# Subsheets_combined.net
KiCad netlist of a schematic drawn in Altium Designer
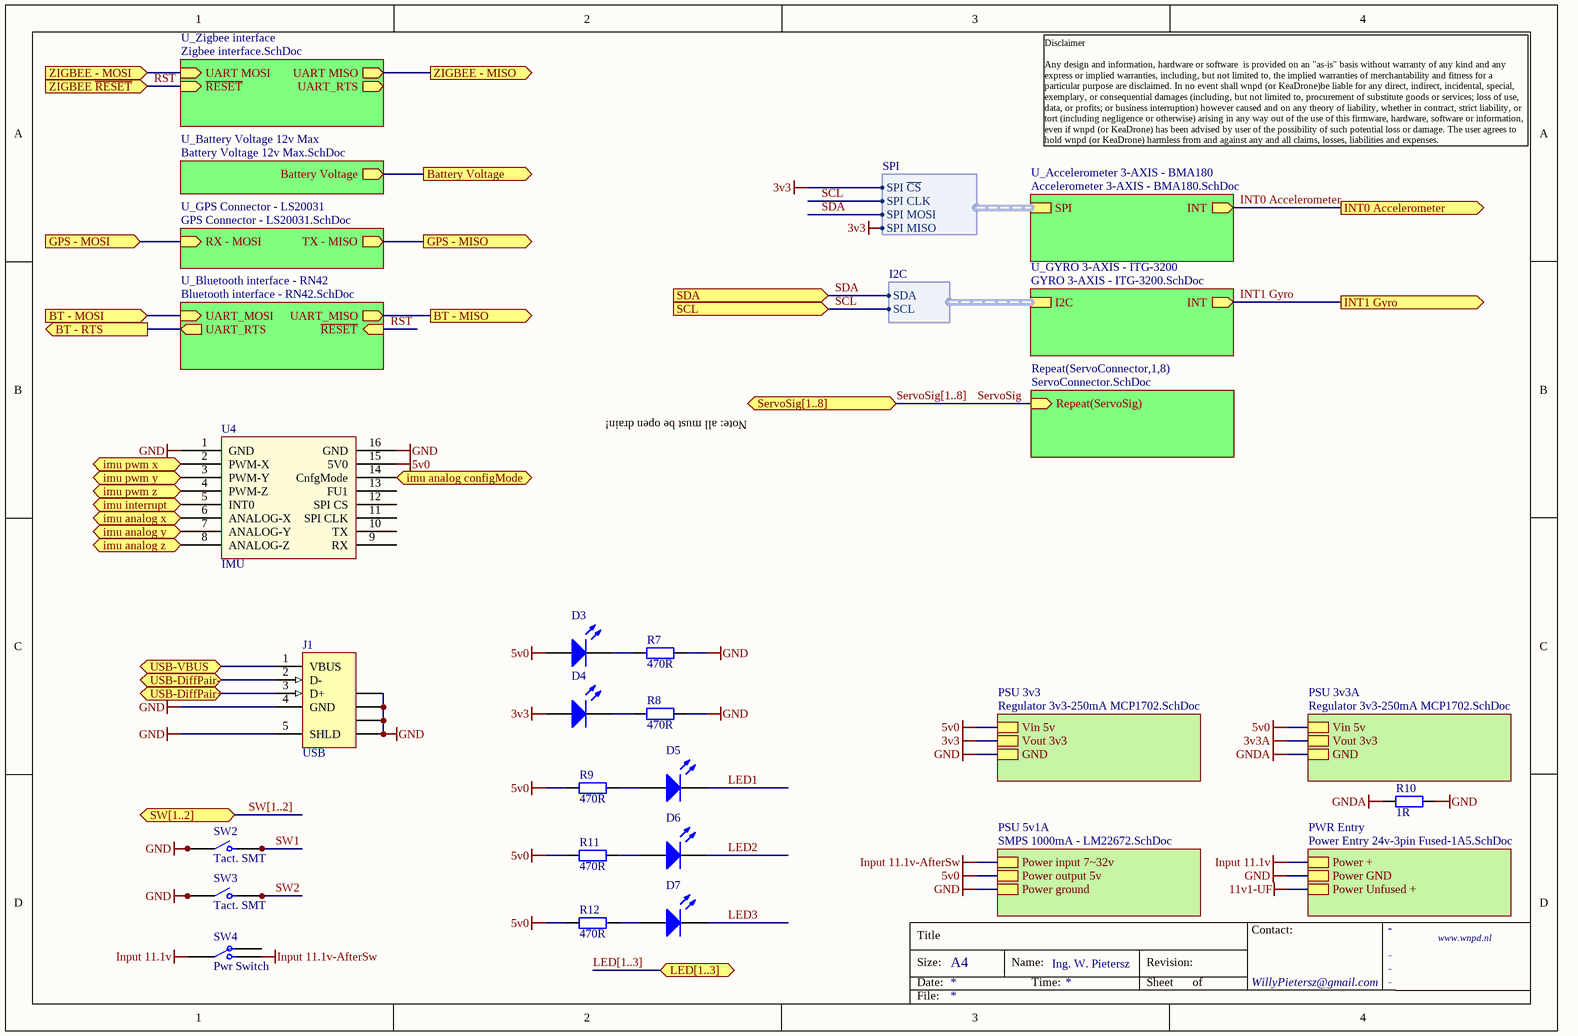
[diagram p0: Subsheets combined.SchDoc]

(export (version "E")
  (design (tool "Eeschema 10.0.6"))
  (components
    (comp (ref "D3")
      (value "~")
      (footprint "PLCC2")
      (description "LED, Surface Mount LED Indicator")
      (fields (field (name "PART NUMBER") "Green-PLCC2") (field (name "AUTHOR") "Willem Pietersz"))
      (libsource (lib "OurDb") (part "LED_SINGLE"))
    )
    (comp (ref "D4")
      (value "~")
      (footprint "PLCC2")
      (description "LED, Surface Mount LED Indicator")
      (fields (field (name "PART NUMBER") "Green-PLCC2") (field (name "AUTHOR") "Willem Pietersz"))
      (libsource (lib "OurDb") (part "LED_SINGLE"))
    )
    (comp (ref "D5")
      (value "~")
      (footprint "PLCC2")
      (description "LED, Surface Mount LED Indicator")
      (fields (field (name "PART NUMBER") "Green-PLCC2") (field (name "AUTHOR") "Willem Pietersz"))
      (libsource (lib "OurDb") (part "LED_SINGLE"))
    )
    (comp (ref "D6")
      (value "~")
      (footprint "PLCC2")
      (description "LED, Surface Mount LED Indicator")
      (fields (field (name "PART NUMBER") "Green-PLCC2") (field (name "AUTHOR") "Willem Pietersz"))
      (libsource (lib "OurDb") (part "LED_SINGLE"))
    )
    (comp (ref "D7")
      (value "~")
      (footprint "PLCC2")
      (description "LED, Surface Mount LED Indicator")
      (fields (field (name "PART NUMBER") "Green-PLCC2") (field (name "AUTHOR") "Willem Pietersz"))
      (libsource (lib "OurDb") (part "LED_SINGLE"))
    )
    (comp (ref "J1")
      (value "USB")
      (footprint "USBminiSMT")
      (description "USBmini 2.0, Right Angle, SMT, B Type, Receptacle, 5 Position, Black")
      (fields
        (field (name "PART NUMBER") "USBmini")
        (field (name "PUBLISHER") "Altium Limited")
        (field (name "AUTHOR") "Willem Pietersz")
      )
      (libsource (lib "OurDb") (part "USBmini"))
    )
    (comp (ref "R7")
      (value "470R")
      (footprint "R0805")
      (description "Resistor")
      (fields
        (field (name "POWER") "0.25W")
        (field (name "TOLERANCE") "0.05")
        (field (name "PUBLISHER") "Altium Limited")
        (field (name "AUTHOR") "Willy Pietersz")
      )
      (libsource (lib "OurDb") (part "RESISTOR"))
    )
    (comp (ref "R8")
      (value "470R")
      (footprint "R0805")
      (description "Resistor")
      (fields
        (field (name "POWER") "0.25W")
        (field (name "TOLERANCE") "0.05")
        (field (name "PUBLISHER") "Altium Limited")
        (field (name "AUTHOR") "Willy Pietersz")
      )
      (libsource (lib "OurDb") (part "RESISTOR"))
    )
    (comp (ref "R9")
      (value "470R")
      (footprint "R0805")
      (description "Resistor")
      (fields
        (field (name "POWER") "0.25W")
        (field (name "TOLERANCE") "0.05")
        (field (name "PUBLISHER") "Altium Limited")
        (field (name "AUTHOR") "Willy Pietersz")
      )
      (libsource (lib "OurDb") (part "RESISTOR"))
    )
    (comp (ref "R10")
      (value "1R")
      (footprint "R0805")
      (description "Resistor")
      (fields
        (field (name "POWER") "0.25W")
        (field (name "TOLERANCE") "0.05")
        (field (name "PUBLISHER") "Altium Limited")
        (field (name "AUTHOR") "Willy Pietersz")
      )
      (libsource (lib "") (part "RESISTOR_1"))
    )
    (comp (ref "R11")
      (value "470R")
      (footprint "R0805")
      (description "Resistor")
      (fields
        (field (name "POWER") "0.25W")
        (field (name "TOLERANCE") "0.05")
        (field (name "PUBLISHER") "Altium Limited")
        (field (name "AUTHOR") "Willy Pietersz")
      )
      (libsource (lib "OurDb") (part "RESISTOR"))
    )
    (comp (ref "R12")
      (value "470R")
      (footprint "R0805")
      (description "Resistor")
      (fields
        (field (name "POWER") "0.25W")
        (field (name "TOLERANCE") "0.05")
        (field (name "PUBLISHER") "Altium Limited")
        (field (name "AUTHOR") "Willy Pietersz")
      )
      (libsource (lib "OurDb") (part "RESISTOR"))
    )
    (comp (ref "SW2")
      (value "Tact. SMT")
      (footprint "SWITCH TACT")
      (description "Switch")
      (fields
        (field (name "PART NUMBER") "Pushbutton TACT")
        (field (name "VOLTAGE") "42")
        (field (name "AUTHOR") "Willem Pietersz")
      )
      (libsource (lib "OurDb") (part "SW-TACT"))
    )
    (comp (ref "SW3")
      (value "Tact. SMT")
      (footprint "SWITCH TACT")
      (description "Switch")
      (fields
        (field (name "PART NUMBER") "Pushbutton TACT")
        (field (name "VOLTAGE") "42")
        (field (name "AUTHOR") "Willem Pietersz")
      )
      (libsource (lib "OurDb") (part "SW-TACT"))
    )
    (comp (ref "SW4")
      (value "Pwr Switch")
      (footprint "1MS1T1B5M1QE")
      (description "Switch")
      (fields (field (name "PART NUMBER") "Toggle-Sw_1MS1T1B5M1QE") (field (name "VOLTAGE") "250"))
      (libsource (lib "OurDb") (part "SW-SPDT"))
    )
    (comp (ref "U4")
      (value "IMU")
      (footprint "Keadrone_IMUv1")
      (fields (field (name "PART NUMBER") "Keadrone-imu-v1"))
      (libsource (lib "OurDb") (part "Keadrone_imu_v1"))
    )
  )
  (nets
    (net (code "19") (name "/LED1") (class "Default")
      (node (ref "D5") (pin "2") (pinfunction "K_2") (pintype "passive"))
    )
    (net (code "20") (name "/LED2") (class "Default")
      (node (ref "D6") (pin "2") (pinfunction "K_2") (pintype "passive"))
    )
    (net (code "21") (name "/LED3") (class "Default")
      (node (ref "D7") (pin "2") (pinfunction "K_2") (pintype "passive"))
    )
    (net (code "26") (name "/SW1") (class "Default")
      (node (ref "SW2") (pin "2") (pintype "passive"))
      (node (ref "SW2") (pin "3") (pintype "passive"))
    )
    (net (code "27") (name "/SW2") (class "Default")
      (node (ref "SW3") (pin "2") (pintype "passive"))
      (node (ref "SW3") (pin "3") (pintype "passive"))
    )
    (net (code "32") (name "/USB-DiffPair+") (class "Default")
      (node (ref "J1") (pin "3") (pinfunction "D+_3") (pintype "input"))
    )
    (net (code "33") (name "/USB-DiffPair-") (class "Default")
      (node (ref "J1") (pin "2") (pinfunction "D-_2") (pintype "input"))
    )
    (net (code "34") (name "/USB-VBUS") (class "Default")
      (node (ref "J1") (pin "1") (pinfunction "VBUS_1") (pintype "power_in"))
    )
    (net (code "37") (name "/imu analog configMode") (class "Default")
      (node (ref "U4") (pin "14") (pinfunction "CnfgMode_14") (pintype "passive"))
    )
    (net (code "38") (name "/imu analog x") (class "Default")
      (node (ref "U4") (pin "6") (pinfunction "ANALOG-X_6") (pintype "passive"))
    )
    (net (code "39") (name "/imu analog y") (class "Default")
      (node (ref "U4") (pin "7") (pinfunction "ANALOG-Y_7") (pintype "passive"))
    )
    (net (code "40") (name "/imu analog z") (class "Default")
      (node (ref "U4") (pin "8") (pinfunction "ANALOG-Z_8") (pintype "passive"))
    )
    (net (code "41") (name "/imu interrupt") (class "Default")
      (node (ref "U4") (pin "5") (pinfunction "INT0_5") (pintype "passive"))
    )
    (net (code "42") (name "/imu pwm x") (class "Default")
      (node (ref "U4") (pin "2") (pinfunction "PWM-X_2") (pintype "passive"))
    )
    (net (code "43") (name "/imu pwm y") (class "Default")
      (node (ref "U4") (pin "3") (pinfunction "PWM-Y_3") (pintype "passive"))
    )
    (net (code "44") (name "/imu pwm z") (class "Default")
      (node (ref "U4") (pin "4") (pinfunction "PWM-Z_4") (pintype "passive"))
    )
    (net (code "47") (name "3v3") (class "Default")
      (node (ref "D4") (pin "1") (pinfunction "A_1") (pintype "passive"))
    )
    (net (code "49") (name "5v0") (class "Default")
      (node (ref "D3") (pin "1") (pinfunction "A_1") (pintype "passive"))
      (node (ref "R11") (pin "2") (pinfunction "2_2") (pintype "passive"))
      (node (ref "R12") (pin "2") (pinfunction "2_2") (pintype "passive"))
      (node (ref "R9") (pin "2") (pinfunction "2_2") (pintype "passive"))
      (node (ref "U4") (pin "15") (pinfunction "5V0_15") (pintype "passive"))
    )
    (net (code "51") (name "GND") (class "Default")
      (node (ref "J1") (pin "4") (pinfunction "GND_4") (pintype "power_in"))
      (node (ref "J1") (pin "5") (pinfunction "SHLD_5") (pintype "passive"))
      (node (ref "J1") (pin "6") (pinfunction "SHLD_6") (pintype "passive"))
      (node (ref "J1") (pin "7") (pinfunction "SHLD_7") (pintype "passive"))
      (node (ref "J1") (pin "8") (pinfunction "SHLD_8") (pintype "passive"))
      (node (ref "J1") (pin "9") (pinfunction "SHLD_9") (pintype "passive"))
      (node (ref "R10") (pin "2") (pinfunction "2_2") (pintype "passive"))
      (node (ref "R7") (pin "1") (pinfunction "1_1") (pintype "passive"))
      (node (ref "R8") (pin "1") (pinfunction "1_1") (pintype "passive"))
      (node (ref "SW2") (pin "1") (pintype "passive"))
      (node (ref "SW2") (pin "4") (pintype "passive"))
      (node (ref "SW3") (pin "1") (pintype "passive"))
      (node (ref "SW3") (pin "4") (pintype "passive"))
      (node (ref "U4") (pin "1") (pinfunction "GND_1") (pintype "passive"))
      (node (ref "U4") (pin "16") (pinfunction "GND_16") (pintype "passive"))
    )
    (net (code "52") (name "GNDA") (class "Default")
      (node (ref "R10") (pin "1") (pinfunction "1_1") (pintype "passive"))
    )
    (net (code "53") (name "Input 11.1v") (class "Default") (node (ref "SW4") (pin "1") (pintype "passive")))
    (net (code "54") (name "Input 11.1v-AfterSw") (class "Default")
      (node (ref "SW4") (pin "2") (pintype "passive"))
    )
    (net (code "55") (name "Net-(D3-K)") (class "Default")
      (node (ref "D3") (pin "2") (pinfunction "K_2") (pintype "passive"))
      (node (ref "R7") (pin "2") (pinfunction "2_2") (pintype "passive"))
    )
    (net (code "56") (name "Net-(D4-K)") (class "Default")
      (node (ref "D4") (pin "2") (pinfunction "K_2") (pintype "passive"))
      (node (ref "R8") (pin "2") (pinfunction "2_2") (pintype "passive"))
    )
    (net (code "57") (name "Net-(D5-A)") (class "Default")
      (node (ref "D5") (pin "1") (pinfunction "A_1") (pintype "passive"))
      (node (ref "R9") (pin "1") (pinfunction "1_1") (pintype "passive"))
    )
    (net (code "58") (name "Net-(D6-A)") (class "Default")
      (node (ref "D6") (pin "1") (pinfunction "A_1") (pintype "passive"))
      (node (ref "R11") (pin "1") (pinfunction "1_1") (pintype "passive"))
    )
    (net (code "59") (name "Net-(D7-A)") (class "Default")
      (node (ref "D7") (pin "1") (pinfunction "A_1") (pintype "passive"))
      (node (ref "R12") (pin "1") (pinfunction "1_1") (pintype "passive"))
    )
    (net (code "60") (name "unconnected-(SW4-Pad3)") (class "Default")
      (node (ref "SW4") (pin "3") (pintype "passive"))
    )
    (net (code "61") (name "unconnected-(U4-FU1-Pad13)") (class "Default")
      (node (ref "U4") (pin "13") (pinfunction "FU1_13") (pintype "passive"))
    )
    (net (code "62") (name "unconnected-(U4-RX-Pad9)") (class "Default")
      (node (ref "U4") (pin "9") (pinfunction "RX_9") (pintype "passive"))
    )
    (net (code "63") (name "unconnected-(U4-SPI_CLK-Pad11)") (class "Default")
      (node (ref "U4") (pin "11") (pinfunction "SPI_CLK_11") (pintype "passive"))
    )
    (net (code "64") (name "unconnected-(U4-SPI_CS-Pad12)") (class "Default")
      (node (ref "U4") (pin "12") (pinfunction "SPI_CS_12") (pintype "passive"))
    )
    (net (code "65") (name "unconnected-(U4-TX-Pad10)") (class "Default")
      (node (ref "U4") (pin "10") (pinfunction "TX_10") (pintype "passive"))
    )
  )
)
